# PWM_Controller_Half_Bridge.net
KiCad netlist of a schematic drawn in Altium Designer
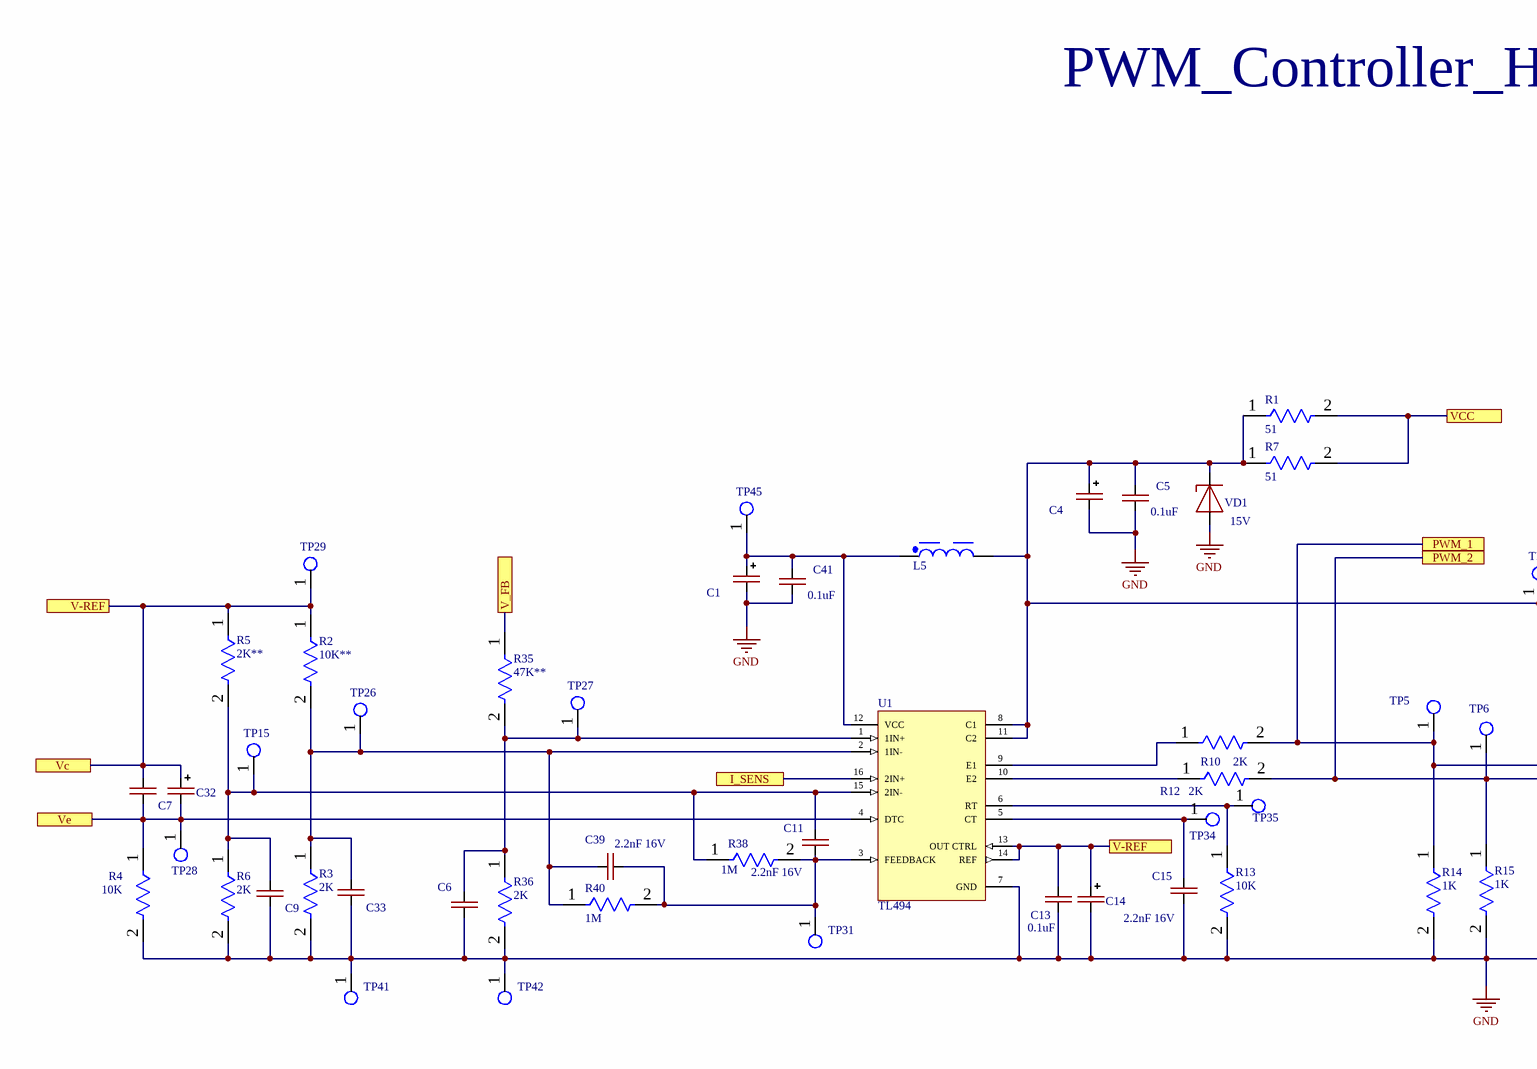
[diagram p0: PWM_Controller_Half_Bridge.SchDoc, left]
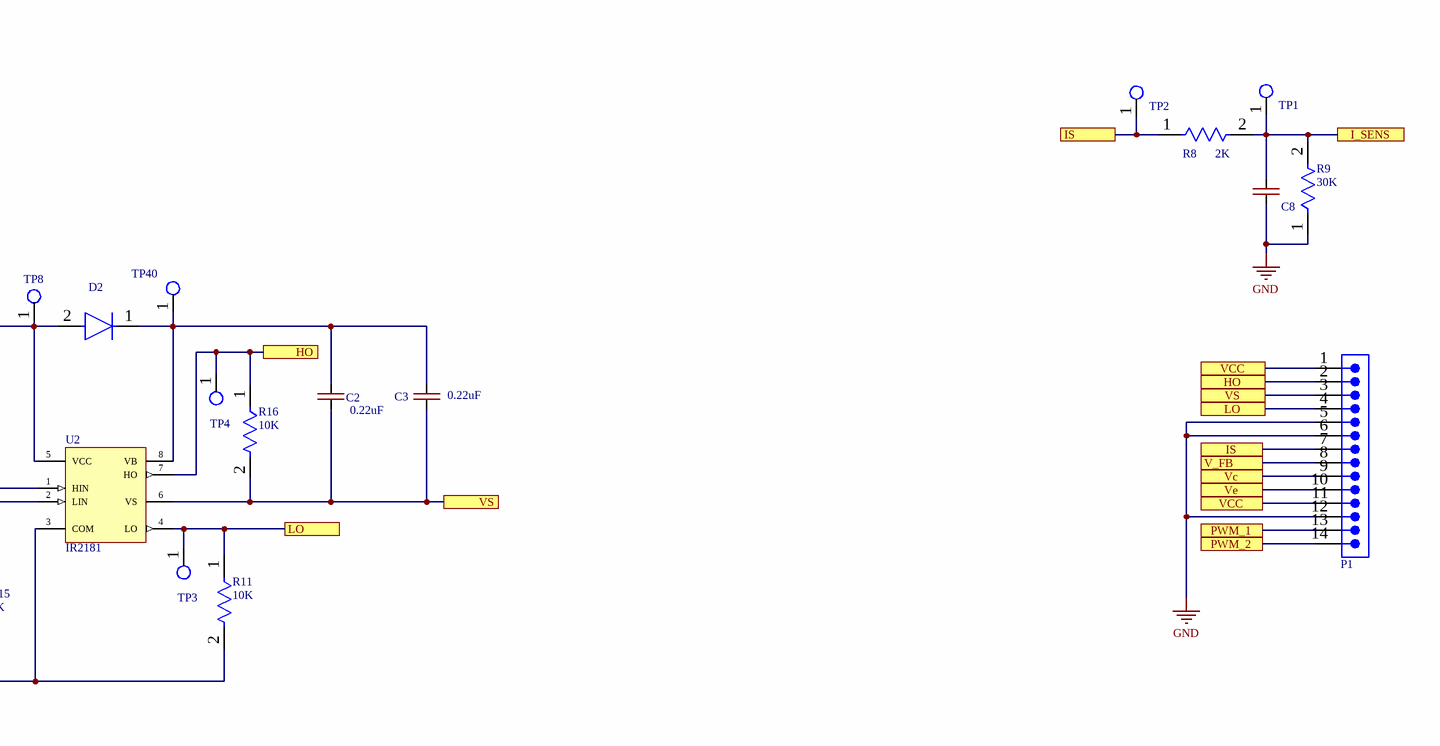
[diagram p1: PWM_Controller_Half_Bridge.SchDoc, right]

(export (version "E")
  (design (tool "Eeschema 10.0.6"))
  (components
    (comp (ref "C1")
      (value "CAP-POLAR")
      (footprint "SIZE_EEE")
      (libsource (lib "PASSIVE_COMPONENTS") (part "CAP-POLAR"))
    )
    (comp (ref "C2")
      (value "0.22uF")
      (footprint "FP-C1210X475K5RACTU-IPC_C")
      (libsource (lib "PASSIVE_COMPONENTS") (part "CAP_1210"))
    )
    (comp (ref "C3")
      (value "0.22uF")
      (footprint "FP-C1210X475K5RACTU-IPC_C")
      (libsource (lib "PASSIVE_COMPONENTS") (part "CAP_1210"))
    )
    (comp (ref "C4")
      (value "CAP-POLAR")
      (footprint "SIZE_EEE")
      (libsource (lib "PASSIVE_COMPONENTS") (part "CAP-POLAR"))
    )
    (comp (ref "C5")
      (value "0.1uF")
      (footprint "CAP-0805")
      (libsource (lib "PASSIVE_COMPONENTS") (part "CAP-NON-POLAR"))
    )
    (comp (ref "C6")
      (value "CAP-NON-POLAR")
      (footprint "CAP-0805")
      (libsource (lib "PASSIVE_COMPONENTS") (part "CAP-NON-POLAR"))
    )
    (comp (ref "C7")
      (value "CAP-NON-POLAR")
      (footprint "CAP-0805")
      (libsource (lib "PASSIVE_COMPONENTS") (part "CAP-NON-POLAR"))
    )
    (comp (ref "C8")
      (value "CAP-NON-POLAR")
      (footprint "CAP-0805")
      (libsource (lib "PASSIVE_COMPONENTS") (part "CAP-NON-POLAR"))
    )
    (comp (ref "C9")
      (value "CAP-NON-POLAR")
      (footprint "CAP-0805")
      (libsource (lib "PASSIVE_COMPONENTS") (part "CAP-NON-POLAR"))
    )
    (comp (ref "C11")
      (value "2.2nF 16V")
      (footprint "CAP-0805")
      (libsource (lib "PASSIVE_COMPONENTS") (part "CAP-NON-POLAR"))
    )
    (comp (ref "C13")
      (value "0.1uF")
      (footprint "CAP-0805")
      (libsource (lib "PASSIVE_COMPONENTS") (part "CAP-NON-POLAR"))
    )
    (comp (ref "C14")
      (value "CAP-POLAR")
      (footprint "SIZE_EEE")
      (libsource (lib "PASSIVE_COMPONENTS") (part "CAP-POLAR"))
    )
    (comp (ref "C15")
      (value "2.2nF 16V")
      (footprint "CAP-0805")
      (libsource (lib "PASSIVE_COMPONENTS") (part "CAP-NON-POLAR"))
    )
    (comp (ref "C32")
      (value "CAP-POLAR")
      (footprint "CAP-TAN-D")
      (libsource (lib "PASSIVE_COMPONENTS") (part "CAP-POLAR"))
    )
    (comp (ref "C33")
      (value "CAP-NON-POLAR")
      (footprint "CAP-0805")
      (libsource (lib "PASSIVE_COMPONENTS") (part "CAP-NON-POLAR"))
    )
    (comp (ref "C39")
      (value "2.2nF 16V")
      (footprint "CAP-0805")
      (libsource (lib "PASSIVE_COMPONENTS") (part "CAP-NON-POLAR"))
    )
    (comp (ref "C41")
      (value "0.1uF")
      (footprint "CAP-0805")
      (libsource (lib "PASSIVE_COMPONENTS") (part "CAP-NON-POLAR"))
    )
    (comp (ref "D2") (value "US1G") (footprint "DO-214AA") (libsource (lib "Diodes") (part "US1G")))
    (comp (ref "L5")
      (value "47µH, 1.17A")
      (footprint "WE-PD2_7850")
      (description "WE-PD2 SMT Power Inductor, size 7850, 47µH, 1.17A, 0.18Ω")
      (fields
        (field (name "MANUFACTURER PART NUMBER") "744775147")
        (field (name "MANUFACTURER") "Wurth Elektronik")
      )
      (libsource (lib "WE-PD2 (rev22d)") (part "744775147"))
    )
    (comp (ref "P1")
      (value "61301411021")
      (footprint "61301411021")
      (description "WR-PHD Pin Header, THT, Angled, pitch 2.54mm, 1 Row, 14P")
      (fields (field (name "MANUFACTURER") "Wurth Elektronik"))
      (libsource (lib "Altium_WR-PHD (rev22b)") (part "61301411021"))
    )
    (comp (ref "R1")
      (value "51")
      (footprint "FP-RMCF1210-MFG")
      (description "51Ω ±5% 0.5W 1210 Thick Film Chip Resistor AEC-Q200 compliant")
      (fields (field (name "TOLERANCE") "5%"))
      (libsource (lib "Altium Content Vault") (part "1029c3af85768c4190bb7ad29bc67b5"))
    )
    (comp (ref "R2")
      (value "10K**")
      (footprint "RES-0805")
      (description "10K")
      (libsource (lib "PASSIVE_COMPONENTS") (part "RES-CONST"))
    )
    (comp (ref "R3")
      (value "2K")
      (footprint "RES-0805")
      (libsource (lib "PASSIVE_COMPONENTS") (part "RES-CONST"))
    )
    (comp (ref "R4")
      (value "10K")
      (footprint "RES-0805")
      (libsource (lib "PASSIVE_COMPONENTS") (part "RES-CONST"))
    )
    (comp (ref "R5")
      (value "2K**")
      (footprint "RES-0805")
      (description "2K")
      (libsource (lib "PASSIVE_COMPONENTS") (part "RES-CONST"))
    )
    (comp (ref "R6")
      (value "2K")
      (footprint "RES-0805")
      (libsource (lib "PASSIVE_COMPONENTS") (part "RES-CONST"))
    )
    (comp (ref "R7")
      (value "51")
      (footprint "FP-RMCF1210-MFG")
      (description "51Ω ±5% 0.5W 1210 Thick Film Chip Resistor AEC-Q200 compliant")
      (fields (field (name "TOLERANCE") "5%"))
      (libsource (lib "Altium Content Vault") (part "1029c3af85768c4190bb7ad29bc67b5"))
    )
    (comp (ref "R8")
      (value "2K")
      (footprint "RES-0805")
      (libsource (lib "PASSIVE_COMPONENTS") (part "RES-CONST"))
    )
    (comp (ref "R9")
      (value "30K")
      (footprint "RES-0805")
      (libsource (lib "PASSIVE_COMPONENTS") (part "RES-CONST"))
    )
    (comp (ref "R10")
      (value "2K")
      (footprint "RES-0805")
      (libsource (lib "PASSIVE_COMPONENTS") (part "RES-CONST"))
    )
    (comp (ref "R11")
      (value "10K")
      (footprint "RES-0805")
      (libsource (lib "PASSIVE_COMPONENTS") (part "RES-CONST"))
    )
    (comp (ref "R12")
      (value "2K")
      (footprint "RES-0805")
      (libsource (lib "PASSIVE_COMPONENTS") (part "RES-CONST"))
    )
    (comp (ref "R13")
      (value "10K")
      (footprint "RES-0805")
      (libsource (lib "PASSIVE_COMPONENTS") (part "RES-CONST"))
    )
    (comp (ref "R14")
      (value "1K")
      (footprint "RES-0805")
      (libsource (lib "PASSIVE_COMPONENTS") (part "RES-CONST"))
    )
    (comp (ref "R15")
      (value "1K")
      (footprint "RES-0805")
      (libsource (lib "PASSIVE_COMPONENTS") (part "RES-CONST"))
    )
    (comp (ref "R16")
      (value "10K")
      (footprint "RES-0805")
      (libsource (lib "PASSIVE_COMPONENTS") (part "RES-CONST"))
    )
    (comp (ref "R35")
      (value "47K**")
      (footprint "RES-0805")
      (description "47K")
      (libsource (lib "PASSIVE_COMPONENTS") (part "RES-CONST"))
    )
    (comp (ref "R36")
      (value "2K")
      (footprint "RES-0805")
      (libsource (lib "PASSIVE_COMPONENTS") (part "RES-CONST"))
    )
    (comp (ref "R38")
      (value "1M")
      (footprint "RES-0805")
      (libsource (lib "PASSIVE_COMPONENTS") (part "RES-CONST"))
    )
    (comp (ref "R40")
      (value "1M")
      (footprint "RES-0805")
      (libsource (lib "PASSIVE_COMPONENTS") (part "RES-CONST"))
    )
    (comp (ref "TP1")
      (value "~")
      (footprint "Test_Point")
      (description "Test_Point")
      (libsource (lib "Connectors") (part "TP_PCB?"))
    )
    (comp (ref "TP2")
      (value "~")
      (footprint "Test_Point")
      (description "Test_Point")
      (libsource (lib "Connectors") (part "TP_PCB?"))
    )
    (comp (ref "TP3")
      (value "~")
      (footprint "Test_Point")
      (description "Test_Point")
      (libsource (lib "Connectors") (part "TP_PCB?"))
    )
    (comp (ref "TP4")
      (value "~")
      (footprint "Test_Point")
      (description "Test_Point")
      (libsource (lib "Connectors") (part "TP_PCB?"))
    )
    (comp (ref "TP5")
      (value "~")
      (footprint "Test_Point")
      (description "Test_Point")
      (libsource (lib "Connectors") (part "TP_PCB?"))
    )
    (comp (ref "TP6")
      (value "~")
      (footprint "Test_Point")
      (description "Test_Point")
      (libsource (lib "Connectors") (part "TP_PCB?"))
    )
    (comp (ref "TP8")
      (value "~")
      (footprint "Test_Point")
      (description "Test_Point")
      (libsource (lib "Connectors") (part "TP_PCB?"))
    )
    (comp (ref "TP15")
      (value "~")
      (footprint "Test_Point")
      (description "Test_Point")
      (libsource (lib "Connectors") (part "TP_PCB?"))
    )
    (comp (ref "TP26")
      (value "~")
      (footprint "Test_Point")
      (description "Test_Point")
      (libsource (lib "Connectors") (part "TP_PCB?"))
    )
    (comp (ref "TP27")
      (value "~")
      (footprint "Test_Point")
      (description "Test_Point")
      (libsource (lib "Connectors") (part "TP_PCB?"))
    )
    (comp (ref "TP28")
      (value "~")
      (footprint "Test_Point")
      (description "Test_Point")
      (libsource (lib "Connectors") (part "TP_PCB?"))
    )
    (comp (ref "TP29")
      (value "~")
      (footprint "Test_Point")
      (description "Test_Point")
      (libsource (lib "Connectors") (part "TP_PCB?"))
    )
    (comp (ref "TP31")
      (value "~")
      (footprint "Test_Point")
      (description "Test_Point")
      (libsource (lib "Connectors") (part "TP_PCB?"))
    )
    (comp (ref "TP34")
      (value "~")
      (footprint "Test_Point")
      (description "Test_Point")
      (libsource (lib "Connectors") (part "TP_PCB?"))
    )
    (comp (ref "TP35")
      (value "~")
      (footprint "Test_Point")
      (description "Test_Point")
      (libsource (lib "Connectors") (part "TP_PCB?"))
    )
    (comp (ref "TP40")
      (value "~")
      (footprint "Test_Point")
      (description "Test_Point")
      (libsource (lib "Connectors") (part "TP_PCB?"))
    )
    (comp (ref "TP41")
      (value "~")
      (footprint "Test_Point")
      (description "Test_Point")
      (libsource (lib "Connectors") (part "TP_PCB?"))
    )
    (comp (ref "TP42")
      (value "~")
      (footprint "Test_Point")
      (description "Test_Point")
      (libsource (lib "Connectors") (part "TP_PCB?"))
    )
    (comp (ref "TP45")
      (value "~")
      (footprint "Test_Point")
      (description "Test_Point")
      (libsource (lib "Connectors") (part "TP_PCB?"))
    )
    (comp (ref "U1")
      (value "TL494")
      (footprint "SOIC-16-M")
      (description "TL494 Pwm controller")
      (libsource (lib "Integrated_Circuts") (part "TL494"))
    )
    (comp (ref "U2")
      (value "IR2181")
      (footprint "SO8-150")
      (description "IR2181 Driver")
      (libsource (lib "Integrated_Circuts") (part "IR2181"))
    )
    (comp (ref "VD1") (value "15V") (footprint "DO-017AA") (libsource (lib "Diodes") (part "ZENER")))
  )
  (nets
    (net (code "1") (name "/HO") (class "Default")
      (node (ref "P1") (pin "2") (pinfunction "2_2") (pintype "passive"))
      (node (ref "R16") (pin "1") (pinfunction "1_1") (pintype "passive"))
      (node (ref "TP4") (pin "1") (pinfunction "G9_1") (pintype "passive"))
      (node (ref "U2") (pin "7") (pinfunction "HO_7") (pintype "output"))
    )
    (net (code "2") (name "/IS") (class "Default")
      (node (ref "P1") (pin "7") (pinfunction "7_7") (pintype "passive"))
      (node (ref "R8") (pin "1") (pinfunction "1_1") (pintype "passive"))
      (node (ref "TP2") (pin "1") (pinfunction "G9_1") (pintype "passive"))
    )
    (net (code "3") (name "/I_SENS") (class "Default")
      (node (ref "C8") (pin "2") (pinfunction "2_2") (pintype "passive"))
      (node (ref "R8") (pin "2") (pinfunction "2_2") (pintype "passive"))
      (node (ref "R9") (pin "2") (pinfunction "2_2") (pintype "passive"))
      (node (ref "TP1") (pin "1") (pinfunction "G9_1") (pintype "passive"))
      (node (ref "U1") (pin "16") (pinfunction "2IN+_16") (pintype "input"))
    )
    (net (code "4") (name "/LO") (class "Default")
      (node (ref "P1") (pin "4") (pinfunction "4_4") (pintype "passive"))
      (node (ref "R11") (pin "1") (pinfunction "1_1") (pintype "passive"))
      (node (ref "TP3") (pin "1") (pinfunction "G9_1") (pintype "passive"))
      (node (ref "U2") (pin "4") (pinfunction "LO_4") (pintype "output"))
    )
    (net (code "5") (name "/PWM_1") (class "Default")
      (node (ref "P1") (pin "13") (pinfunction "13_13") (pintype "passive"))
      (node (ref "R10") (pin "2") (pinfunction "2_2") (pintype "passive"))
      (node (ref "R14") (pin "1") (pinfunction "1_1") (pintype "passive"))
      (node (ref "TP5") (pin "1") (pinfunction "G9_1") (pintype "passive"))
      (node (ref "U2") (pin "1") (pinfunction "HIN_1") (pintype "input"))
    )
    (net (code "6") (name "/PWM_2") (class "Default")
      (node (ref "P1") (pin "14") (pinfunction "14_14") (pintype "passive"))
      (node (ref "R12") (pin "2") (pinfunction "2_2") (pintype "passive"))
      (node (ref "R15") (pin "1") (pinfunction "1_1") (pintype "passive"))
      (node (ref "TP6") (pin "1") (pinfunction "G9_1") (pintype "passive"))
      (node (ref "U2") (pin "2") (pinfunction "LIN_2") (pintype "input"))
    )
    (net (code "7") (name "/V-REF") (class "Default")
      (node (ref "C13") (pin "2") (pinfunction "2_2") (pintype "passive"))
      (node (ref "C14") (pin "1") (pinfunction "+_1") (pintype "passive"))
      (node (ref "C32") (pin "1") (pinfunction "+_1") (pintype "passive"))
      (node (ref "C7") (pin "2") (pinfunction "2_2") (pintype "passive"))
      (node (ref "P1") (pin "9") (pinfunction "9_9") (pintype "passive"))
      (node (ref "R2") (pin "1") (pinfunction "1_1") (pintype "passive"))
      (node (ref "R5") (pin "1") (pinfunction "1_1") (pintype "passive"))
      (node (ref "TP29") (pin "1") (pinfunction "G9_1") (pintype "passive"))
      (node (ref "U1") (pin "13") (pinfunction "OUT_CTRL_13") (pintype "input"))
      (node (ref "U1") (pin "14") (pinfunction "REF_14") (pintype "output"))
    )
    (net (code "8") (name "/VCC") (class "Default")
      (node (ref "P1") (pin "1") (pinfunction "1_1") (pintype "passive"))
      (node (ref "P1") (pin "11") (pinfunction "11_11") (pintype "passive"))
      (node (ref "R1") (pin "2") (pinfunction "2_2") (pintype "passive"))
      (node (ref "R7") (pin "2") (pinfunction "2_2") (pintype "passive"))
    )
    (net (code "9") (name "/VS") (class "Default")
      (node (ref "C2") (pin "1") (pinfunction "1_1") (pintype "passive"))
      (node (ref "C3") (pin "1") (pinfunction "1_1") (pintype "passive"))
      (node (ref "P1") (pin "3") (pinfunction "3_3") (pintype "passive"))
      (node (ref "R16") (pin "2") (pinfunction "2_2") (pintype "passive"))
      (node (ref "U2") (pin "6") (pinfunction "VS_6") (pintype "power_in"))
    )
    (net (code "10") (name "/V_FB") (class "Default")
      (node (ref "P1") (pin "8") (pinfunction "8_8") (pintype "passive"))
      (node (ref "R35") (pin "1") (pinfunction "1_1") (pintype "passive"))
    )
    (net (code "11") (name "/Ve") (class "Default")
      (node (ref "C32") (pin "2") (pinfunction "-_2") (pintype "passive"))
      (node (ref "C7") (pin "1") (pinfunction "1_1") (pintype "passive"))
      (node (ref "P1") (pin "10") (pinfunction "10_10") (pintype "passive"))
      (node (ref "R4") (pin "1") (pinfunction "1_1") (pintype "passive"))
      (node (ref "TP28") (pin "1") (pinfunction "G9_1") (pintype "passive"))
      (node (ref "U1") (pin "4") (pinfunction "DTC_4") (pintype "input"))
    )
    (net (code "12") (name "GND") (class "Default")
      (node (ref "C1") (pin "2") (pinfunction "-_2") (pintype "passive"))
      (node (ref "C13") (pin "1") (pinfunction "1_1") (pintype "passive"))
      (node (ref "C14") (pin "2") (pinfunction "-_2") (pintype "passive"))
      (node (ref "C15") (pin "1") (pinfunction "1_1") (pintype "passive"))
      (node (ref "C33") (pin "1") (pinfunction "1_1") (pintype "passive"))
      (node (ref "C4") (pin "2") (pinfunction "-_2") (pintype "passive"))
      (node (ref "C41") (pin "1") (pinfunction "1_1") (pintype "passive"))
      (node (ref "C5") (pin "1") (pinfunction "1_1") (pintype "passive"))
      (node (ref "C6") (pin "1") (pinfunction "1_1") (pintype "passive"))
      (node (ref "C8") (pin "1") (pinfunction "1_1") (pintype "passive"))
      (node (ref "C9") (pin "1") (pinfunction "1_1") (pintype "passive"))
      (node (ref "P1") (pin "12") (pinfunction "12_12") (pintype "passive"))
      (node (ref "P1") (pin "5") (pinfunction "5_5") (pintype "passive"))
      (node (ref "P1") (pin "6") (pinfunction "6_6") (pintype "passive"))
      (node (ref "R11") (pin "2") (pinfunction "2_2") (pintype "passive"))
      (node (ref "R13") (pin "2") (pinfunction "2_2") (pintype "passive"))
      (node (ref "R14") (pin "2") (pinfunction "2_2") (pintype "passive"))
      (node (ref "R15") (pin "2") (pinfunction "2_2") (pintype "passive"))
      (node (ref "R3") (pin "2") (pinfunction "2_2") (pintype "passive"))
      (node (ref "R36") (pin "2") (pinfunction "2_2") (pintype "passive"))
      (node (ref "R4") (pin "2") (pinfunction "2_2") (pintype "passive"))
      (node (ref "R6") (pin "2") (pinfunction "2_2") (pintype "passive"))
      (node (ref "R9") (pin "1") (pinfunction "1_1") (pintype "passive"))
      (node (ref "TP41") (pin "1") (pinfunction "G9_1") (pintype "passive"))
      (node (ref "TP42") (pin "1") (pinfunction "G9_1") (pintype "passive"))
      (node (ref "U1") (pin "7") (pinfunction "GND_7") (pintype "power_in"))
      (node (ref "U2") (pin "3") (pinfunction "COM_3") (pintype "passive"))
      (node (ref "VD1") (pin "2") (pinfunction "A_2") (pintype "passive"))
    )
    (net (code "13") (name "Net-(C1-+)") (class "Default")
      (node (ref "C1") (pin "1") (pinfunction "+_1") (pintype "passive"))
      (node (ref "C41") (pin "2") (pinfunction "2_2") (pintype "passive"))
      (node (ref "L5") (pin "1") (pinfunction "1_1") (pintype "passive"))
      (node (ref "TP45") (pin "1") (pinfunction "G9_1") (pintype "passive"))
      (node (ref "U1") (pin "12") (pinfunction "VCC_12") (pintype "power_in"))
    )
    (net (code "14") (name "Net-(C4-+)") (class "Default")
      (node (ref "C4") (pin "1") (pinfunction "+_1") (pintype "passive"))
      (node (ref "C5") (pin "2") (pinfunction "2_2") (pintype "passive"))
      (node (ref "D2") (pin "2") (pinfunction "A_2") (pintype "passive"))
      (node (ref "L5") (pin "2") (pinfunction "2_2") (pintype "passive"))
      (node (ref "R1") (pin "1") (pinfunction "1_1") (pintype "passive"))
      (node (ref "R7") (pin "1") (pinfunction "1_1") (pintype "passive"))
      (node (ref "TP8") (pin "1") (pinfunction "G9_1") (pintype "passive"))
      (node (ref "U1") (pin "11") (pinfunction "C2_11") (pintype "passive"))
      (node (ref "U1") (pin "8") (pinfunction "C1_8") (pintype "passive"))
      (node (ref "U2") (pin "5") (pinfunction "VCC_5") (pintype "power_in"))
      (node (ref "VD1") (pin "1") (pinfunction "C_1") (pintype "passive"))
    )
    (net (code "15") (name "Net-(D2-C)") (class "Default")
      (node (ref "C2") (pin "2") (pinfunction "2_2") (pintype "passive"))
      (node (ref "C3") (pin "2") (pinfunction "2_2") (pintype "passive"))
      (node (ref "D2") (pin "1") (pinfunction "C_1") (pintype "passive"))
      (node (ref "TP40") (pin "1") (pinfunction "G9_1") (pintype "passive"))
      (node (ref "U2") (pin "8") (pinfunction "VB_8") (pintype "power_in"))
    )
    (net (code "16") (name "Net-(TP15-G9)") (class "Default")
      (node (ref "C11") (pin "2") (pinfunction "2_2") (pintype "passive"))
      (node (ref "C9") (pin "2") (pinfunction "2_2") (pintype "passive"))
      (node (ref "R38") (pin "1") (pinfunction "1_1") (pintype "passive"))
      (node (ref "R5") (pin "2") (pinfunction "2_2") (pintype "passive"))
      (node (ref "R6") (pin "1") (pinfunction "1_1") (pintype "passive"))
      (node (ref "TP15") (pin "1") (pinfunction "G9_1") (pintype "passive"))
      (node (ref "U1") (pin "15") (pinfunction "2IN-_15") (pintype "input"))
    )
    (net (code "17") (name "Net-(TP26-G9)") (class "Default")
      (node (ref "C33") (pin "2") (pinfunction "2_2") (pintype "passive"))
      (node (ref "C39") (pin "2") (pinfunction "2_2") (pintype "passive"))
      (node (ref "R2") (pin "2") (pinfunction "2_2") (pintype "passive"))
      (node (ref "R3") (pin "1") (pinfunction "1_1") (pintype "passive"))
      (node (ref "R40") (pin "1") (pinfunction "1_1") (pintype "passive"))
      (node (ref "TP26") (pin "1") (pinfunction "G9_1") (pintype "passive"))
      (node (ref "U1") (pin "2") (pinfunction "1IN-_2") (pintype "input"))
    )
    (net (code "18") (name "Net-(TP27-G9)") (class "Default")
      (node (ref "C6") (pin "2") (pinfunction "2_2") (pintype "passive"))
      (node (ref "R35") (pin "2") (pinfunction "2_2") (pintype "passive"))
      (node (ref "R36") (pin "1") (pinfunction "1_1") (pintype "passive"))
      (node (ref "TP27") (pin "1") (pinfunction "G9_1") (pintype "passive"))
      (node (ref "U1") (pin "1") (pinfunction "1IN+_1") (pintype "input"))
    )
    (net (code "19") (name "Net-(TP31-G9)") (class "Default")
      (node (ref "C11") (pin "1") (pinfunction "1_1") (pintype "passive"))
      (node (ref "C39") (pin "1") (pinfunction "1_1") (pintype "passive"))
      (node (ref "R38") (pin "2") (pinfunction "2_2") (pintype "passive"))
      (node (ref "R40") (pin "2") (pinfunction "2_2") (pintype "passive"))
      (node (ref "TP31") (pin "1") (pinfunction "G9_1") (pintype "passive"))
      (node (ref "U1") (pin "3") (pinfunction "FEEDBACK_3") (pintype "input"))
    )
    (net (code "20") (name "Net-(TP34-G9)") (class "Default")
      (node (ref "C15") (pin "2") (pinfunction "2_2") (pintype "passive"))
      (node (ref "TP34") (pin "1") (pinfunction "G9_1") (pintype "passive"))
      (node (ref "U1") (pin "5") (pinfunction "CT_5") (pintype "passive"))
    )
    (net (code "21") (name "Net-(TP35-G9)") (class "Default")
      (node (ref "R13") (pin "1") (pinfunction "1_1") (pintype "passive"))
      (node (ref "TP35") (pin "1") (pinfunction "G9_1") (pintype "passive"))
      (node (ref "U1") (pin "6") (pinfunction "RT_6") (pintype "passive"))
    )
    (net (code "22") (name "Net-(U1-E1)") (class "Default")
      (node (ref "R10") (pin "1") (pinfunction "1_1") (pintype "passive"))
      (node (ref "U1") (pin "9") (pinfunction "E1_9") (pintype "passive"))
    )
    (net (code "23") (name "Net-(U1-E2)") (class "Default")
      (node (ref "R12") (pin "1") (pinfunction "1_1") (pintype "passive"))
      (node (ref "U1") (pin "10") (pinfunction "E2_10") (pintype "passive"))
    )
  )
)
